# 12V_Load_Switches.net
KiCad netlist of a schematic drawn in Altium Designer
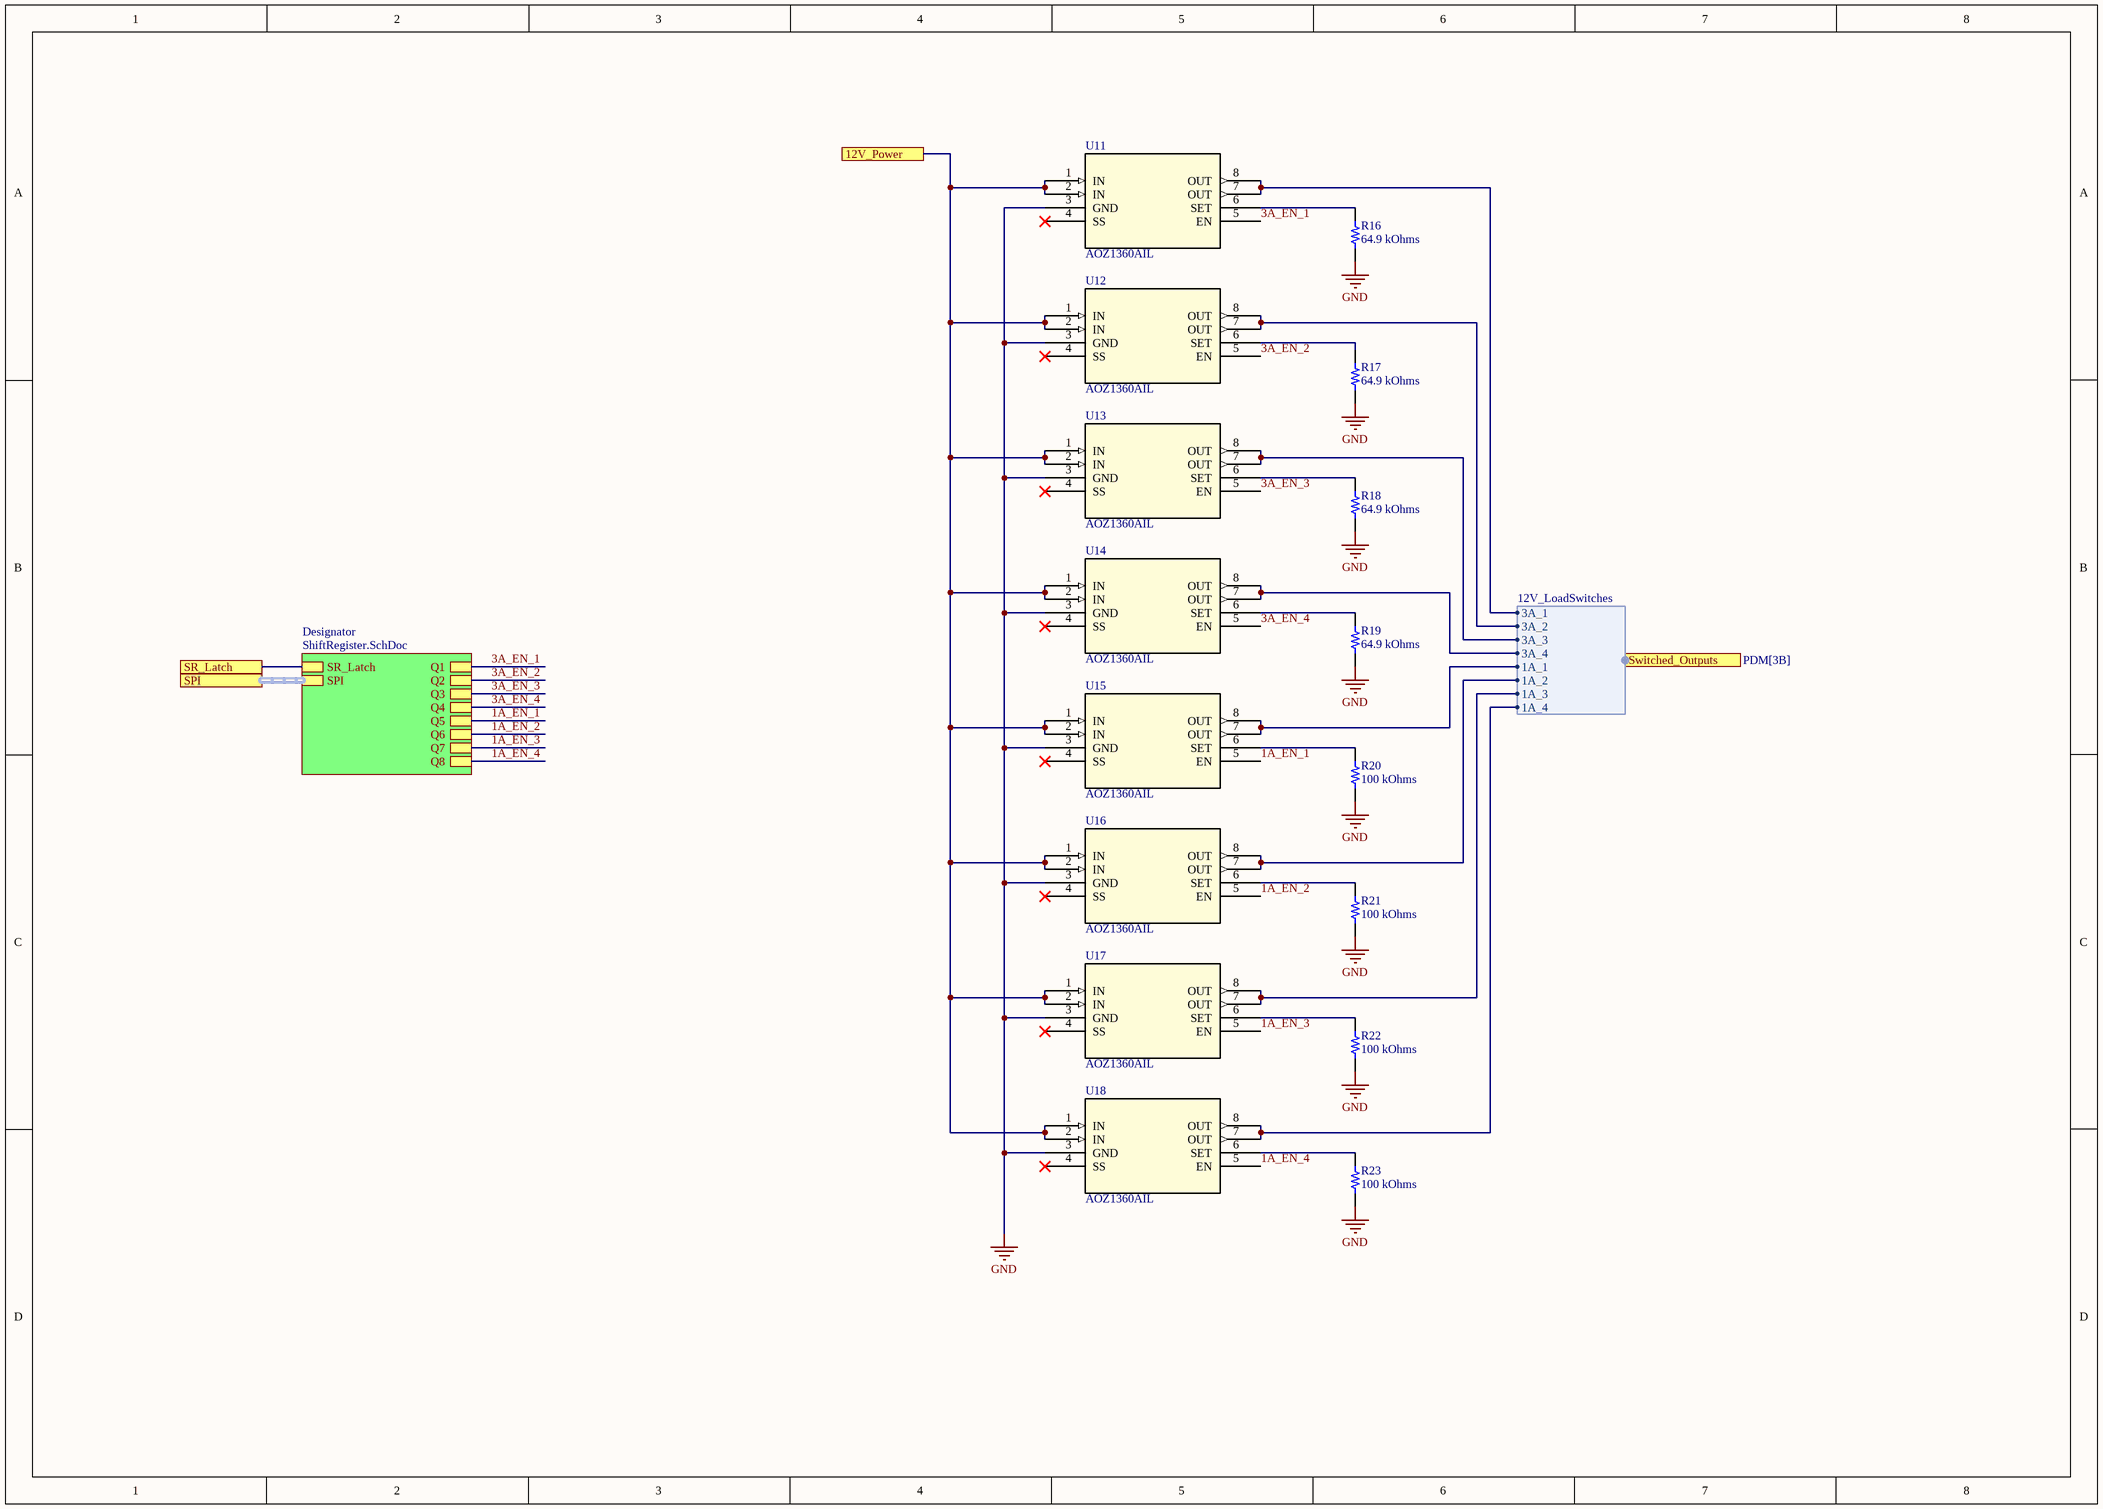
[diagram p0: 12V_Load_Switches.SchDoc]

(export (version "E")
  (design (tool "Eeschema 10.0.6"))
  (components
    (comp (ref "R16")
      (value "64.9 kOhms")
      (footprint "RES 0603_1608")
      (description "RES SMD 64.9K OHM 0.1% 1/6W 0603")
      (fields
        (field (name "PART NUMBER") "7-2176089-3")
        (field (name "MANUFACTURER") "TE Connectivity Passive Product")
      )
      (libsource (lib "altium_library") (part "Resistor"))
    )
    (comp (ref "R17")
      (value "64.9 kOhms")
      (footprint "RES 0603_1608")
      (description "RES SMD 64.9K OHM 0.1% 1/6W 0603")
      (fields
        (field (name "PART NUMBER") "7-2176089-3")
        (field (name "MANUFACTURER") "TE Connectivity Passive Product")
      )
      (libsource (lib "altium_library") (part "Resistor"))
    )
    (comp (ref "R18")
      (value "64.9 kOhms")
      (footprint "RES 0603_1608")
      (description "RES SMD 64.9K OHM 0.1% 1/6W 0603")
      (fields
        (field (name "PART NUMBER") "7-2176089-3")
        (field (name "MANUFACTURER") "TE Connectivity Passive Product")
      )
      (libsource (lib "altium_library") (part "Resistor"))
    )
    (comp (ref "R19")
      (value "64.9 kOhms")
      (footprint "RES 0603_1608")
      (description "RES SMD 64.9K OHM 0.1% 1/6W 0603")
      (fields
        (field (name "PART NUMBER") "7-2176089-3")
        (field (name "MANUFACTURER") "TE Connectivity Passive Product")
      )
      (libsource (lib "altium_library") (part "Resistor"))
    )
    (comp (ref "R20")
      (value "100 kOhms")
      (footprint "RES 0603_1608")
      (description "RES SMD 100K OHM 1% 1/10W 0603")
      (fields (field (name "PART NUMBER") "AA0603FR-07100KL") (field (name "MANUFACTURER") "Yageo"))
      (libsource (lib "altium_library") (part "Resistor"))
    )
    (comp (ref "R21")
      (value "100 kOhms")
      (footprint "RES 0603_1608")
      (description "RES SMD 100K OHM 1% 1/10W 0603")
      (fields (field (name "PART NUMBER") "AA0603FR-07100KL") (field (name "MANUFACTURER") "Yageo"))
      (libsource (lib "altium_library") (part "Resistor"))
    )
    (comp (ref "R22")
      (value "100 kOhms")
      (footprint "RES 0603_1608")
      (description "RES SMD 100K OHM 1% 1/10W 0603")
      (fields (field (name "PART NUMBER") "AA0603FR-07100KL") (field (name "MANUFACTURER") "Yageo"))
      (libsource (lib "altium_library") (part "Resistor"))
    )
    (comp (ref "R23")
      (value "100 kOhms")
      (footprint "RES 0603_1608")
      (description "RES SMD 100K OHM 1% 1/10W 0603")
      (fields (field (name "PART NUMBER") "AA0603FR-07100KL") (field (name "MANUFACTURER") "Yageo"))
      (libsource (lib "altium_library") (part "Resistor"))
    )
    (comp (ref "U11")
      (value "AOZ1360AIL")
      (footprint "AOZ1360AIL_AOS")
      (description "No Description Available")
      (fields (field (name "COPYRIGHT") "Copyright (C) 2023 Ultra Librarian. All rights reserved."))
      (libsource (lib "AOZ1360AIL") (part "AOZ1360AIL"))
    )
    (comp (ref "U12")
      (value "AOZ1360AIL")
      (footprint "AOZ1360AIL_AOS")
      (description "No Description Available")
      (fields (field (name "COPYRIGHT") "Copyright (C) 2023 Ultra Librarian. All rights reserved."))
      (libsource (lib "AOZ1360AIL") (part "AOZ1360AIL"))
    )
    (comp (ref "U13")
      (value "AOZ1360AIL")
      (footprint "AOZ1360AIL_AOS")
      (description "No Description Available")
      (fields (field (name "COPYRIGHT") "Copyright (C) 2023 Ultra Librarian. All rights reserved."))
      (libsource (lib "AOZ1360AIL") (part "AOZ1360AIL"))
    )
    (comp (ref "U14")
      (value "AOZ1360AIL")
      (footprint "AOZ1360AIL_AOS")
      (description "No Description Available")
      (fields (field (name "COPYRIGHT") "Copyright (C) 2023 Ultra Librarian. All rights reserved."))
      (libsource (lib "AOZ1360AIL") (part "AOZ1360AIL"))
    )
    (comp (ref "U15")
      (value "AOZ1360AIL")
      (footprint "AOZ1360AIL_AOS")
      (description "No Description Available")
      (fields (field (name "COPYRIGHT") "Copyright (C) 2023 Ultra Librarian. All rights reserved."))
      (libsource (lib "AOZ1360AIL") (part "AOZ1360AIL"))
    )
    (comp (ref "U16")
      (value "AOZ1360AIL")
      (footprint "AOZ1360AIL_AOS")
      (description "No Description Available")
      (fields (field (name "COPYRIGHT") "Copyright (C) 2023 Ultra Librarian. All rights reserved."))
      (libsource (lib "AOZ1360AIL") (part "AOZ1360AIL"))
    )
    (comp (ref "U17")
      (value "AOZ1360AIL")
      (footprint "AOZ1360AIL_AOS")
      (description "No Description Available")
      (fields (field (name "COPYRIGHT") "Copyright (C) 2023 Ultra Librarian. All rights reserved."))
      (libsource (lib "AOZ1360AIL") (part "AOZ1360AIL"))
    )
    (comp (ref "U18")
      (value "AOZ1360AIL")
      (footprint "AOZ1360AIL_AOS")
      (description "No Description Available")
      (fields (field (name "COPYRIGHT") "Copyright (C) 2023 Ultra Librarian. All rights reserved."))
      (libsource (lib "AOZ1360AIL") (part "AOZ1360AIL"))
    )
  )
  (nets
    (net (code "3") (name "/1A_EN_1") (class "Default")
      (node (ref "U15") (pin "5") (pinfunction "EN_5") (pintype "passive"))
    )
    (net (code "4") (name "/1A_EN_2") (class "Default")
      (node (ref "U16") (pin "5") (pinfunction "EN_5") (pintype "passive"))
    )
    (net (code "5") (name "/1A_EN_3") (class "Default")
      (node (ref "U17") (pin "5") (pinfunction "EN_5") (pintype "passive"))
    )
    (net (code "6") (name "/1A_EN_4") (class "Default")
      (node (ref "U18") (pin "5") (pinfunction "EN_5") (pintype "passive"))
    )
    (net (code "7") (name "/3A_EN_1") (class "Default")
      (node (ref "U11") (pin "5") (pinfunction "EN_5") (pintype "passive"))
    )
    (net (code "8") (name "/3A_EN_2") (class "Default")
      (node (ref "U12") (pin "5") (pinfunction "EN_5") (pintype "passive"))
    )
    (net (code "9") (name "/3A_EN_3") (class "Default")
      (node (ref "U13") (pin "5") (pinfunction "EN_5") (pintype "passive"))
    )
    (net (code "10") (name "/3A_EN_4") (class "Default")
      (node (ref "U14") (pin "5") (pinfunction "EN_5") (pintype "passive"))
    )
    (net (code "11") (name "/12V_Power") (class "Default")
      (node (ref "U11") (pin "1") (pinfunction "IN_1") (pintype "input"))
      (node (ref "U11") (pin "2") (pinfunction "IN_2") (pintype "input"))
      (node (ref "U12") (pin "1") (pinfunction "IN_1") (pintype "input"))
      (node (ref "U12") (pin "2") (pinfunction "IN_2") (pintype "input"))
      (node (ref "U13") (pin "1") (pinfunction "IN_1") (pintype "input"))
      (node (ref "U13") (pin "2") (pinfunction "IN_2") (pintype "input"))
      (node (ref "U14") (pin "1") (pinfunction "IN_1") (pintype "input"))
      (node (ref "U14") (pin "2") (pinfunction "IN_2") (pintype "input"))
      (node (ref "U15") (pin "1") (pinfunction "IN_1") (pintype "input"))
      (node (ref "U15") (pin "2") (pinfunction "IN_2") (pintype "input"))
      (node (ref "U16") (pin "1") (pinfunction "IN_1") (pintype "input"))
      (node (ref "U16") (pin "2") (pinfunction "IN_2") (pintype "input"))
      (node (ref "U17") (pin "1") (pinfunction "IN_1") (pintype "input"))
      (node (ref "U17") (pin "2") (pinfunction "IN_2") (pintype "input"))
      (node (ref "U18") (pin "1") (pinfunction "IN_1") (pintype "input"))
      (node (ref "U18") (pin "2") (pinfunction "IN_2") (pintype "input"))
    )
    (net (code "15") (name "GND") (class "Default")
      (node (ref "R16") (pin "1") (pinfunction "1_1") (pintype "passive"))
      (node (ref "R17") (pin "1") (pinfunction "1_1") (pintype "passive"))
      (node (ref "R18") (pin "1") (pinfunction "1_1") (pintype "passive"))
      (node (ref "R19") (pin "1") (pinfunction "1_1") (pintype "passive"))
      (node (ref "R20") (pin "1") (pinfunction "1_1") (pintype "passive"))
      (node (ref "R21") (pin "1") (pinfunction "1_1") (pintype "passive"))
      (node (ref "R22") (pin "1") (pinfunction "1_1") (pintype "passive"))
      (node (ref "R23") (pin "1") (pinfunction "1_1") (pintype "passive"))
      (node (ref "U11") (pin "3") (pinfunction "GND_3") (pintype "power_in"))
      (node (ref "U12") (pin "3") (pinfunction "GND_3") (pintype "power_in"))
      (node (ref "U13") (pin "3") (pinfunction "GND_3") (pintype "power_in"))
      (node (ref "U14") (pin "3") (pinfunction "GND_3") (pintype "power_in"))
      (node (ref "U15") (pin "3") (pinfunction "GND_3") (pintype "power_in"))
      (node (ref "U16") (pin "3") (pinfunction "GND_3") (pintype "power_in"))
      (node (ref "U17") (pin "3") (pinfunction "GND_3") (pintype "power_in"))
      (node (ref "U18") (pin "3") (pinfunction "GND_3") (pintype "power_in"))
    )
    (net (code "16") (name "Net-(U11-OUT-Pad7)") (class "Default")
      (node (ref "U11") (pin "7") (pinfunction "OUT_7") (pintype "output"))
      (node (ref "U11") (pin "8") (pinfunction "OUT_8") (pintype "output"))
    )
    (net (code "17") (name "Net-(U11-SET)") (class "Default")
      (node (ref "R16") (pin "2") (pinfunction "2_2") (pintype "passive"))
      (node (ref "U11") (pin "6") (pinfunction "SET_6") (pintype "passive"))
    )
    (net (code "18") (name "Net-(U12-OUT-Pad7)") (class "Default")
      (node (ref "U12") (pin "7") (pinfunction "OUT_7") (pintype "output"))
      (node (ref "U12") (pin "8") (pinfunction "OUT_8") (pintype "output"))
    )
    (net (code "19") (name "Net-(U12-SET)") (class "Default")
      (node (ref "R17") (pin "2") (pinfunction "2_2") (pintype "passive"))
      (node (ref "U12") (pin "6") (pinfunction "SET_6") (pintype "passive"))
    )
    (net (code "20") (name "Net-(U13-OUT-Pad7)") (class "Default")
      (node (ref "U13") (pin "7") (pinfunction "OUT_7") (pintype "output"))
      (node (ref "U13") (pin "8") (pinfunction "OUT_8") (pintype "output"))
    )
    (net (code "21") (name "Net-(U13-SET)") (class "Default")
      (node (ref "R18") (pin "2") (pinfunction "2_2") (pintype "passive"))
      (node (ref "U13") (pin "6") (pinfunction "SET_6") (pintype "passive"))
    )
    (net (code "22") (name "Net-(U14-OUT-Pad7)") (class "Default")
      (node (ref "U14") (pin "7") (pinfunction "OUT_7") (pintype "output"))
      (node (ref "U14") (pin "8") (pinfunction "OUT_8") (pintype "output"))
    )
    (net (code "23") (name "Net-(U14-SET)") (class "Default")
      (node (ref "R19") (pin "2") (pinfunction "2_2") (pintype "passive"))
      (node (ref "U14") (pin "6") (pinfunction "SET_6") (pintype "passive"))
    )
    (net (code "24") (name "Net-(U15-OUT-Pad7)") (class "Default")
      (node (ref "U15") (pin "7") (pinfunction "OUT_7") (pintype "output"))
      (node (ref "U15") (pin "8") (pinfunction "OUT_8") (pintype "output"))
    )
    (net (code "25") (name "Net-(U15-SET)") (class "Default")
      (node (ref "R20") (pin "2") (pinfunction "2_2") (pintype "passive"))
      (node (ref "U15") (pin "6") (pinfunction "SET_6") (pintype "passive"))
    )
    (net (code "26") (name "Net-(U16-OUT-Pad7)") (class "Default")
      (node (ref "U16") (pin "7") (pinfunction "OUT_7") (pintype "output"))
      (node (ref "U16") (pin "8") (pinfunction "OUT_8") (pintype "output"))
    )
    (net (code "27") (name "Net-(U16-SET)") (class "Default")
      (node (ref "R21") (pin "2") (pinfunction "2_2") (pintype "passive"))
      (node (ref "U16") (pin "6") (pinfunction "SET_6") (pintype "passive"))
    )
    (net (code "28") (name "Net-(U17-OUT-Pad7)") (class "Default")
      (node (ref "U17") (pin "7") (pinfunction "OUT_7") (pintype "output"))
      (node (ref "U17") (pin "8") (pinfunction "OUT_8") (pintype "output"))
    )
    (net (code "29") (name "Net-(U17-SET)") (class "Default")
      (node (ref "R22") (pin "2") (pinfunction "2_2") (pintype "passive"))
      (node (ref "U17") (pin "6") (pinfunction "SET_6") (pintype "passive"))
    )
    (net (code "30") (name "Net-(U18-OUT-Pad7)") (class "Default")
      (node (ref "U18") (pin "7") (pinfunction "OUT_7") (pintype "output"))
      (node (ref "U18") (pin "8") (pinfunction "OUT_8") (pintype "output"))
    )
    (net (code "31") (name "Net-(U18-SET)") (class "Default")
      (node (ref "R23") (pin "2") (pinfunction "2_2") (pintype "passive"))
      (node (ref "U18") (pin "6") (pinfunction "SET_6") (pintype "passive"))
    )
    (net (code "32") (name "unconnected-(U11-SS-Pad4)") (class "Default")
      (node (ref "U11") (pin "4") (pinfunction "SS_4") (pintype "passive+no_connect"))
    )
    (net (code "33") (name "unconnected-(U12-SS-Pad4)") (class "Default")
      (node (ref "U12") (pin "4") (pinfunction "SS_4") (pintype "passive+no_connect"))
    )
    (net (code "34") (name "unconnected-(U13-SS-Pad4)") (class "Default")
      (node (ref "U13") (pin "4") (pinfunction "SS_4") (pintype "passive+no_connect"))
    )
    (net (code "35") (name "unconnected-(U14-SS-Pad4)") (class "Default")
      (node (ref "U14") (pin "4") (pinfunction "SS_4") (pintype "passive+no_connect"))
    )
    (net (code "36") (name "unconnected-(U15-SS-Pad4)") (class "Default")
      (node (ref "U15") (pin "4") (pinfunction "SS_4") (pintype "passive+no_connect"))
    )
    (net (code "37") (name "unconnected-(U16-SS-Pad4)") (class "Default")
      (node (ref "U16") (pin "4") (pinfunction "SS_4") (pintype "passive+no_connect"))
    )
    (net (code "38") (name "unconnected-(U17-SS-Pad4)") (class "Default")
      (node (ref "U17") (pin "4") (pinfunction "SS_4") (pintype "passive+no_connect"))
    )
    (net (code "39") (name "unconnected-(U18-SS-Pad4)") (class "Default")
      (node (ref "U18") (pin "4") (pinfunction "SS_4") (pintype "passive+no_connect"))
    )
  )
)
